# BOB_v1_02.net
KiCad netlist of a schematic drawn in EAGLE
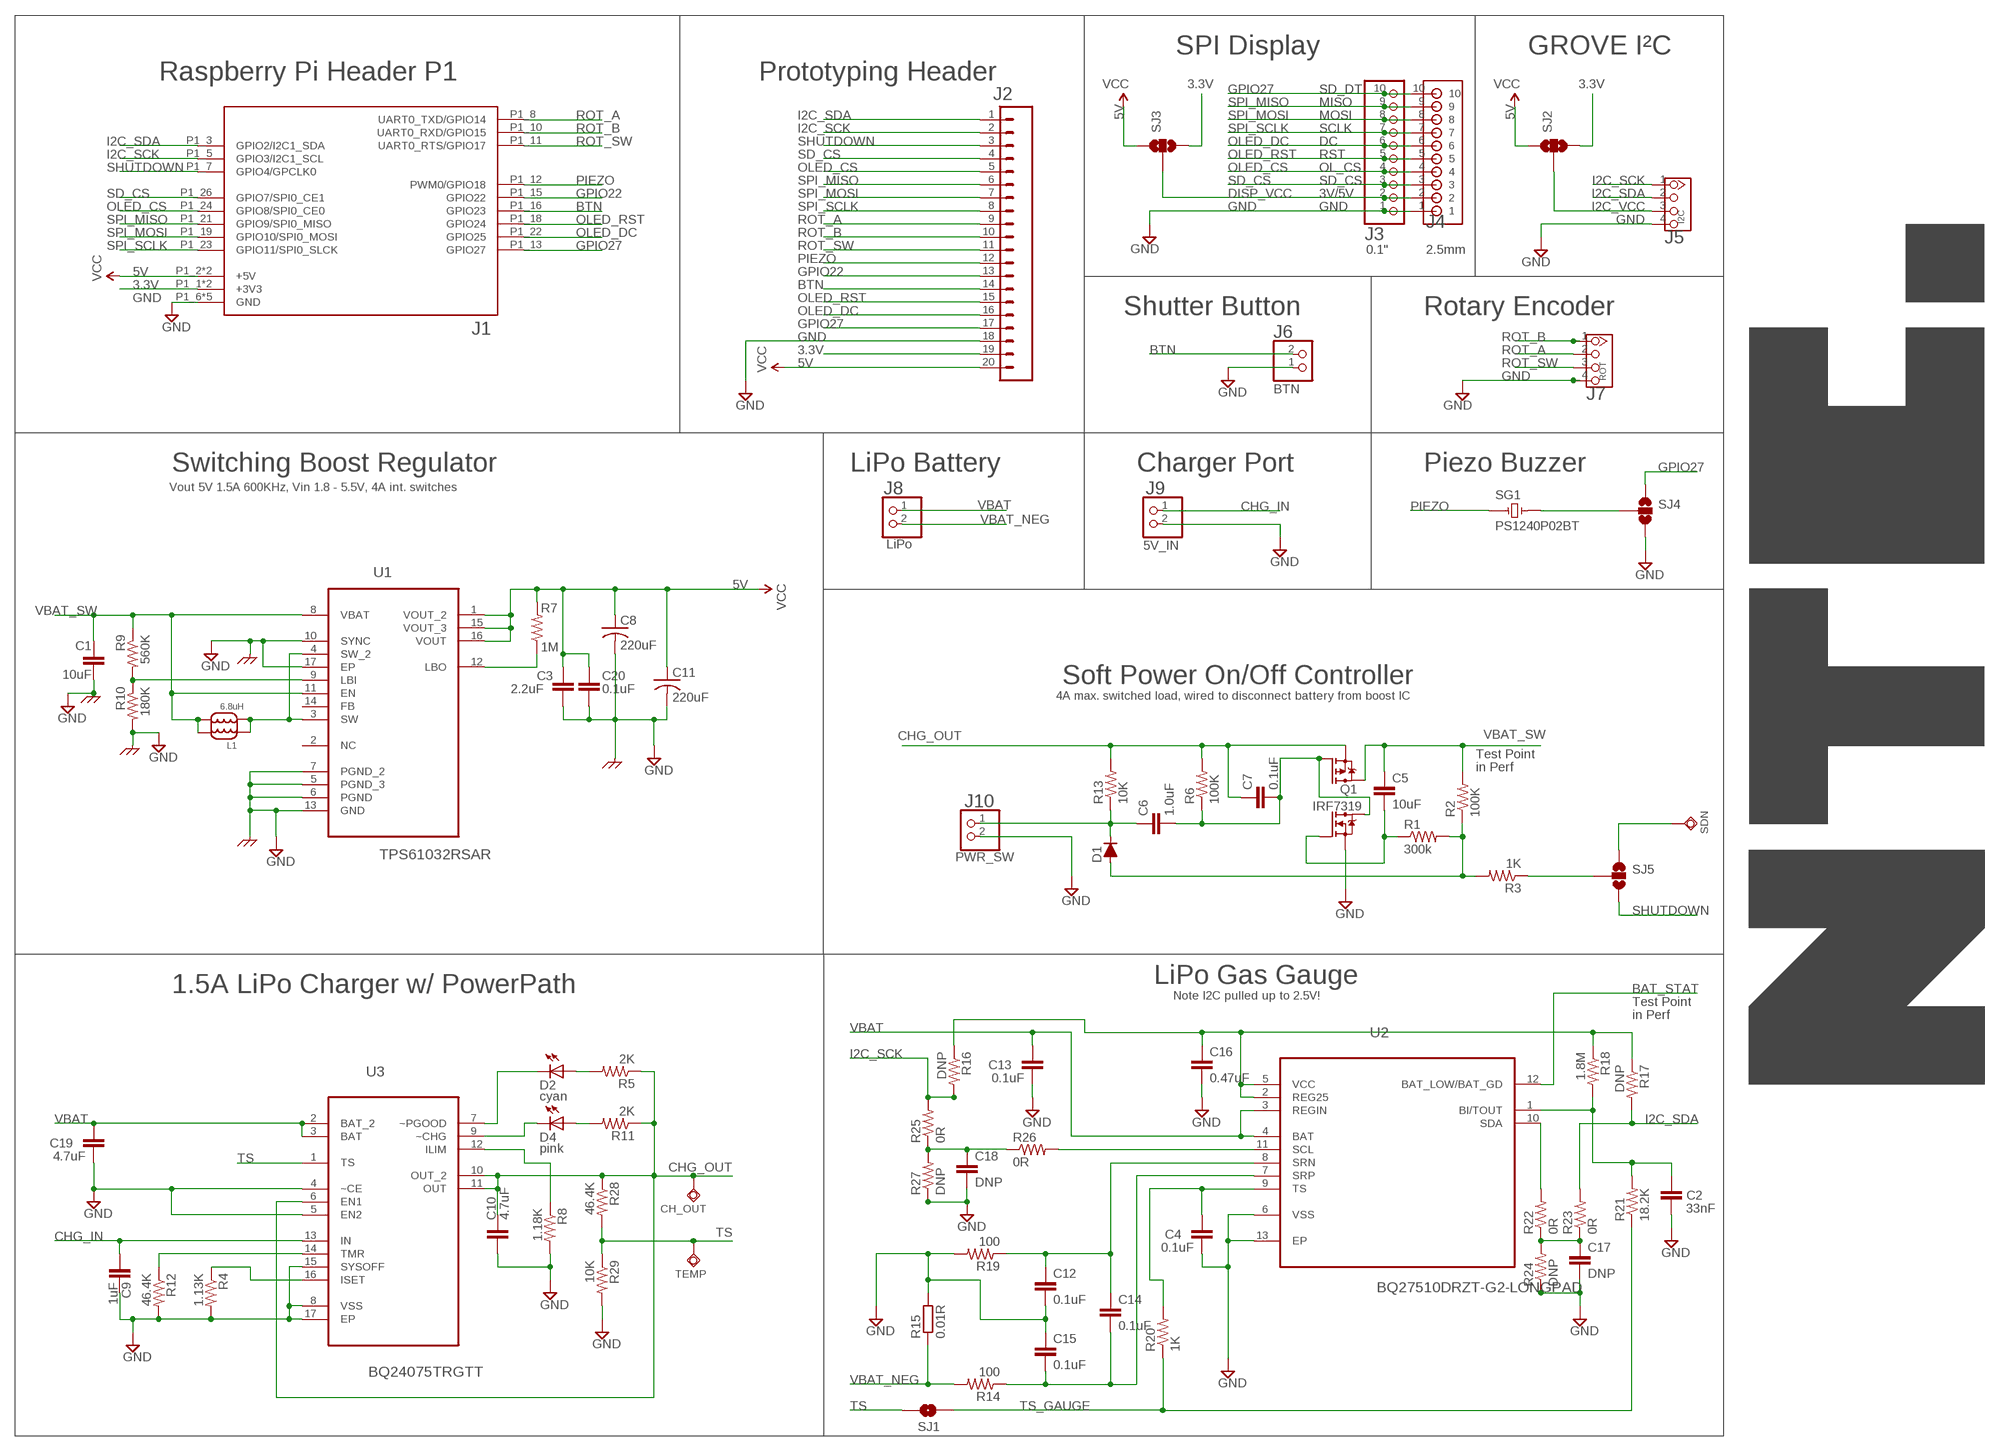
[diagram p0: schematic, sheet 1]

(export (version "E")
  (design (tool "Eeschema 10.0.6"))
  (components
    (comp (ref "C1")
      (value "10uF")
      (footprint "eagle-import:1206")
      (libsource (lib "eagle-import") (part "CAP1206"))
    )
    (comp (ref "C2")
      (value "33nF")
      (footprint "eagle-import:0603-CAP")
      (libsource (lib "eagle-import") (part "CAP0603-CAP"))
    )
    (comp (ref "C3")
      (value "2.2uF")
      (footprint "eagle-import:0603")
      (libsource (lib "eagle-import") (part "CAP0603"))
    )
    (comp (ref "C4")
      (value "0.1uF")
      (footprint "eagle-import:0603-CAP")
      (libsource (lib "eagle-import") (part "CAP0603-CAP"))
    )
    (comp (ref "C5")
      (value "10uF")
      (footprint "eagle-import:0603-CAP")
      (libsource (lib "eagle-import") (part "10UF-6.3V-20%(0603)"))
    )
    (comp (ref "C6")
      (value "1.0uF")
      (footprint "eagle-import:0603-CAP")
      (libsource (lib "eagle-import") (part "1.0UF-16V-10%(0603)"))
    )
    (comp (ref "C7")
      (value "0.1uF")
      (footprint "eagle-import:0603-CAP")
      (libsource (lib "eagle-import") (part "0.1UF-25V-5%(0603)"))
    )
    (comp (ref "C8")
      (value "220uF")
      (footprint "eagle-import:C1210")
      (libsource (lib "eagle-import") (part "C-USC1210"))
    )
    (comp (ref "C9")
      (value "1uF")
      (footprint "eagle-import:0603-CAP")
      (libsource (lib "eagle-import") (part "CAP0603-CAP"))
    )
    (comp (ref "C10")
      (value "4.7uF")
      (footprint "eagle-import:0603-CAP")
      (libsource (lib "eagle-import") (part "CAP0603-CAP"))
    )
    (comp (ref "C11")
      (value "220uF")
      (footprint "eagle-import:C1210")
      (libsource (lib "eagle-import") (part "C-USC1210"))
    )
    (comp (ref "C12")
      (value "0.1uF")
      (footprint "eagle-import:0603-CAP")
      (libsource (lib "eagle-import") (part "SparkFun-Capacitors_CAP0603-CAP"))
    )
    (comp (ref "C13")
      (value "0.1uF")
      (footprint "eagle-import:0603-CAP")
      (libsource (lib "eagle-import") (part "CAP0603-CAP"))
    )
    (comp (ref "C14")
      (value "0.1uF")
      (footprint "eagle-import:0603-CAP")
      (libsource (lib "eagle-import") (part "SparkFun-Capacitors_CAP0603-CAP"))
    )
    (comp (ref "C15")
      (value "0.1uF")
      (footprint "eagle-import:0603-CAP")
      (libsource (lib "eagle-import") (part "SparkFun-Capacitors_CAP0603-CAP"))
    )
    (comp (ref "C16")
      (value "0.47uF")
      (footprint "eagle-import:0603-CAP")
      (libsource (lib "eagle-import") (part "SparkFun-Capacitors_CAP0603-CAP"))
    )
    (comp (ref "C17")
      (value "DNP")
      (footprint "eagle-import:0603-CAP")
      (libsource (lib "eagle-import") (part "SparkFun-Capacitors_CAP0603-CAP"))
    )
    (comp (ref "C18")
      (value "DNP")
      (footprint "eagle-import:0603-CAP")
      (libsource (lib "eagle-import") (part "SparkFun-Capacitors_CAP0603-CAP"))
    )
    (comp (ref "C19")
      (value "4.7uF")
      (footprint "eagle-import:0603-CAP")
      (libsource (lib "eagle-import") (part "CAP0603-CAP"))
    )
    (comp (ref "C20")
      (value "0.1uF")
      (footprint "eagle-import:0603-CAP")
      (fields (field (name "PROD_ID") "CAP-00868"))
      (libsource (lib "eagle-import") (part "1.0UF-16V-10%(0603)"))
    )
    (comp (ref "CH_OUT")
      (value "TP1.2")
      (footprint "eagle-import:TP_1.2")
      (libsource (lib "eagle-import") (part "TP1.2"))
    )
    (comp (ref "D1")
      (value "D-FILL-SMB")
      (footprint "eagle-import:SMB")
      (libsource (lib "eagle-import") (part "D-FILL-SMB"))
    )
    (comp (ref "D2")
      (value "cyan")
      (footprint "eagle-import:LED-0603")
      (libsource (lib "eagle-import") (part "LED0603"))
    )
    (comp (ref "D4")
      (value "pink")
      (footprint "eagle-import:LED-0603")
      (libsource (lib "eagle-import") (part "LED0603"))
    )
    (comp (ref "J1")
      (value "PICAM_RPI-B-PICAM")
      (footprint "eagle-import:PICAM_RPI-B-PICAM")
      (libsource (lib "eagle-import") (part "PICAM_RPI-B-PICAM"))
    )
    (comp (ref "J2")
      (value "M20LOCK_LONGPADS")
      (footprint "eagle-import:1X20_LOCK_LONGPADS")
      (libsource (lib "eagle-import") (part "M20LOCK_LONGPADS"))
    )
    (comp (ref "J3")
      (value "PINHD-1X10")
      (footprint "eagle-import:1X10-BIG")
      (libsource (lib "eagle-import") (part "PINHD-1X10"))
    )
    (comp (ref "J4")
      (value "B10B-EH-A-RA")
      (footprint "eagle-import:S10B-EH")
      (libsource (lib "eagle-import") (part "B10B-EH-A-RA"))
    )
    (comp (ref "J5")
      (value "I2C")
      (footprint "eagle-import:4P-2.0")
      (libsource (lib "eagle-import") (part "TWIG-4P-2.0-2.0"))
    )
    (comp (ref "J6")
      (value "BTN")
      (footprint "eagle-import:PICAM_JST-PH-2-THM")
      (libsource (lib "eagle-import") (part "PICAM_JST_2PIN-THM"))
    )
    (comp (ref "J7")
      (value "ROT")
      (footprint "eagle-import:4P-2.0")
      (libsource (lib "eagle-import") (part "TWIG-4P-2.0-2.0"))
    )
    (comp (ref "J8")
      (value "LiPo")
      (footprint "eagle-import:PICAM_JST-PH-2-THM")
      (libsource (lib "eagle-import") (part "PICAM_JST_2PIN-THM"))
    )
    (comp (ref "J9")
      (value "5V_IN")
      (footprint "eagle-import:PICAM_JST-PH-2-THM")
      (libsource (lib "eagle-import") (part "PICAM_JST_2PIN-THM"))
    )
    (comp (ref "J10")
      (value "PWR_SW")
      (footprint "eagle-import:PICAM_JST-PH-2-THM")
      (libsource (lib "eagle-import") (part "PICAM_JST_2PIN-THM"))
    )
    (comp (ref "L1")
      (value "6.8uH")
      (footprint "eagle-import:SUMIDA_CDRH124")
      (libsource (lib "eagle-import") (part "SUMIDA_CDRH124CDRH124NP-6R8MC"))
    )
    (comp (ref "Q1")
      (value "IRF7319")
      (footprint "eagle-import:SO08-IRF")
      (libsource (lib "eagle-import") (part "IRF7319Q"))
    )
    (comp (ref "R1")
      (value "300k")
      (footprint "eagle-import:0603-RES")
      (libsource (lib "eagle-import") (part "SparkFun-Passives_RESISTOR0603-RES"))
    )
    (comp (ref "R2")
      (value "100K")
      (footprint "eagle-import:0603-RES")
      (libsource (lib "eagle-import") (part "SparkFun-Passives_RESISTOR0603-RES"))
    )
    (comp (ref "R3")
      (value "1K")
      (footprint "eagle-import:0603-RES")
      (libsource (lib "eagle-import") (part "SparkFun-Passives_RESISTOR0603-RES"))
    )
    (comp (ref "R4")
      (value "1.13K")
      (footprint "eagle-import:0603-RES")
      (libsource (lib "eagle-import") (part "RESISTOR0603-RES"))
    )
    (comp (ref "R5")
      (value "2K")
      (footprint "eagle-import:0603-RES")
      (libsource (lib "eagle-import") (part "RESISTOR0603-RES"))
    )
    (comp (ref "R6")
      (value "100K")
      (footprint "eagle-import:0603-RES")
      (libsource (lib "eagle-import") (part "SparkFun-Passives_RESISTOR0603-RES"))
    )
    (comp (ref "R7")
      (value "1M")
      (footprint "eagle-import:0603-RES")
      (libsource (lib "eagle-import") (part "RESISTOR0603-RES"))
    )
    (comp (ref "R8")
      (value "1.18K")
      (footprint "eagle-import:0603-RES")
      (libsource (lib "eagle-import") (part "RESISTOR0603-RES"))
    )
    (comp (ref "R9")
      (value "560K")
      (footprint "eagle-import:0603-RES")
      (libsource (lib "eagle-import") (part "RESISTOR0603-RES"))
    )
    (comp (ref "R10")
      (value "180K")
      (footprint "eagle-import:0603-RES")
      (libsource (lib "eagle-import") (part "RESISTOR0603-RES"))
    )
    (comp (ref "R11")
      (value "2K")
      (footprint "eagle-import:0603-RES")
      (libsource (lib "eagle-import") (part "RESISTOR0603-RES"))
    )
    (comp (ref "R12")
      (value "46.4K")
      (footprint "eagle-import:0603-RES")
      (libsource (lib "eagle-import") (part "RESISTOR0603-RES"))
    )
    (comp (ref "R13")
      (value "10K")
      (footprint "eagle-import:0603-RES")
      (libsource (lib "eagle-import") (part "SparkFun-Passives_RESISTOR0603-RES"))
    )
    (comp (ref "R14")
      (value "100")
      (footprint "eagle-import:0603-RES")
      (libsource (lib "eagle-import") (part "RESISTOR0603-RES"))
    )
    (comp (ref "R15")
      (value "0.01R")
      (footprint "eagle-import:R1206")
      (libsource (lib "eagle-import") (part "RESISTOR-1206"))
    )
    (comp (ref "R16")
      (value "DNP")
      (footprint "eagle-import:0603-RES")
      (libsource (lib "eagle-import") (part "RESISTOR0603-RES"))
    )
    (comp (ref "R17")
      (value "DNP")
      (footprint "eagle-import:0603-RES")
      (libsource (lib "eagle-import") (part "RESISTOR0603-RES"))
    )
    (comp (ref "R18")
      (value "1.8M")
      (footprint "eagle-import:0603-RES")
      (libsource (lib "eagle-import") (part "RESISTOR0603-RES"))
    )
    (comp (ref "R19")
      (value "100")
      (footprint "eagle-import:0603-RES")
      (libsource (lib "eagle-import") (part "RESISTOR0603-RES"))
    )
    (comp (ref "R20")
      (value "1K")
      (footprint "eagle-import:0603-RES")
      (libsource (lib "eagle-import") (part "SparkFun-Resistors_RESISTOR0603-RES"))
    )
    (comp (ref "R21")
      (value "18.2K")
      (footprint "eagle-import:0603-RES")
      (libsource (lib "eagle-import") (part "SparkFun-Resistors_RESISTOR0603-RES"))
    )
    (comp (ref "R22")
      (value "0R")
      (footprint "eagle-import:0603-RES")
      (libsource (lib "eagle-import") (part "SparkFun-Resistors_RESISTOR0603-RES"))
    )
    (comp (ref "R23")
      (value "0R")
      (footprint "eagle-import:0603-RES")
      (libsource (lib "eagle-import") (part "SparkFun-Resistors_RESISTOR0603-RES"))
    )
    (comp (ref "R24")
      (value "DNP")
      (footprint "eagle-import:0603-RES")
      (libsource (lib "eagle-import") (part "SparkFun-Resistors_RESISTOR0603-RES"))
    )
    (comp (ref "R25")
      (value "0R")
      (footprint "eagle-import:0603-RES")
      (libsource (lib "eagle-import") (part "SparkFun-Resistors_RESISTOR0603-RES"))
    )
    (comp (ref "R26")
      (value "0R")
      (footprint "eagle-import:0603-RES")
      (libsource (lib "eagle-import") (part "SparkFun-Resistors_RESISTOR0603-RES"))
    )
    (comp (ref "R27")
      (value "DNP")
      (footprint "eagle-import:0603-RES")
      (libsource (lib "eagle-import") (part "SparkFun-Resistors_RESISTOR0603-RES"))
    )
    (comp (ref "R28")
      (value "46.4K")
      (footprint "eagle-import:0603-RES")
      (libsource (lib "eagle-import") (part "RESISTOR0603-RES"))
    )
    (comp (ref "R29")
      (value "10K")
      (footprint "eagle-import:0603-RES")
      (libsource (lib "eagle-import") (part "RESISTOR0603-RES"))
    )
    (comp (ref "SDN")
      (value "TP1.2")
      (footprint "eagle-import:TP_1.2")
      (libsource (lib "eagle-import") (part "TP1.2"))
    )
    (comp (ref "SG1")
      (value "PS1240P02BT")
      (footprint "eagle-import:PS1240")
      (libsource (lib "eagle-import") (part "PS1240P02BT"))
    )
    (comp (ref "SJ1")
      (value "SOLDERJUMPER-OLDTRACE")
      (footprint "eagle-import:SJ_2S-TRACE")
      (libsource (lib "eagle-import") (part "SOLDERJUMPER-OLDTRACE"))
    )
    (comp (ref "SJ2")
      (value "SOLDERJUMPER_2WAYPASTE1&2")
      (footprint "eagle-import:SJ_3_PASTE1&2")
      (libsource (lib "eagle-import") (part "SOLDERJUMPER_2WAYPASTE1&2"))
    )
    (comp (ref "SJ3")
      (value "SOLDERJUMPER_2WAYPASTE2&3")
      (footprint "eagle-import:SJ_3_PASTE2&3")
      (libsource (lib "eagle-import") (part "SOLDERJUMPER_2WAYPASTE2&3"))
    )
    (comp (ref "SJ4")
      (value "SOLDERJUMPER_2WAYPASTE1&2")
      (footprint "eagle-import:SJ_3_PASTE1&2")
      (libsource (lib "eagle-import") (part "SOLDERJUMPER_2WAYPASTE1&2"))
    )
    (comp (ref "SJ5")
      (value "SOLDERJUMPER_2WAYPASTE2&3")
      (footprint "eagle-import:SJ_3_PASTE2&3")
      (libsource (lib "eagle-import") (part "SOLDERJUMPER_2WAYPASTE2&3"))
    )
    (comp (ref "TEMP")
      (value "TP1.2")
      (footprint "eagle-import:TP_1.2")
      (libsource (lib "eagle-import") (part "TP1.2"))
    )
    (comp (ref "U1")
      (value "TPS61032RSAR")
      (footprint "eagle-import:QFN65P400X400X100-17N")
      (libsource (lib "eagle-import") (part "TPS61032RSAR"))
    )
    (comp (ref "U2")
      (value "BQ27510DRZT-G2-LONGPAD")
      (footprint "eagle-import:SON40P400X250X100-13N+LONGPAD")
      (fields (field (name "MPN") "BQ27510DRZT-G2") (field (name "SUPPLIER") "Texas Inustruments"))
      (libsource (lib "eagle-import") (part "BQ27510DRZT-G2-LONGPAD"))
    )
    (comp (ref "U3")
      (value "BQ24075TRGTT")
      (footprint "eagle-import:QFN50P300X300X100-17N")
      (libsource (lib "eagle-import") (part "BQ24075TRGTT"))
    )
  )
  (nets
    (net (code "1") (name "3.3V") (class "Default")
      (node (ref "J1") (pin "P1_1") (pinfunction "+3V3_P1_1") (pintype "power_in"))
      (node (ref "J1") (pin "P1_17") (pinfunction "+3V3_P1_17") (pintype "power_in"))
      (node (ref "J2") (pin "19") (pinfunction "19_19") (pintype "passive"))
      (node (ref "SJ2") (pin "3") (pinfunction "3_3") (pintype "passive"))
      (node (ref "SJ3") (pin "3") (pinfunction "3_3") (pintype "passive"))
    )
    (net (code "2") (name "5V") (class "Default")
      (node (ref "C11") (pin "1") (pinfunction "1_1") (pintype "passive"))
      (node (ref "C20") (pin "1") (pinfunction "1_1") (pintype "passive"))
      (node (ref "C3") (pin "1") (pinfunction "1_1") (pintype "passive"))
      (node (ref "C8") (pin "1") (pinfunction "1_1") (pintype "passive"))
      (node (ref "J1") (pin "P1_2") (pinfunction "+5V_P1_2") (pintype "power_in"))
      (node (ref "J1") (pin "P1_4") (pinfunction "+5V_P1_4") (pintype "power_in"))
      (node (ref "J2") (pin "20") (pinfunction "20_20") (pintype "passive"))
      (node (ref "R7") (pin "2") (pinfunction "2_2") (pintype "passive"))
      (node (ref "SJ2") (pin "1") (pinfunction "1_1") (pintype "passive"))
      (node (ref "SJ3") (pin "1") (pinfunction "1_1") (pintype "passive"))
      (node (ref "U1") (pin "1") (pinfunction "VOUT_2_1") (pintype "output"))
      (node (ref "U1") (pin "15") (pinfunction "VOUT_3_15") (pintype "output"))
      (node (ref "U1") (pin "16") (pinfunction "VOUT_16") (pintype "output"))
    )
    (net (code "3") (name "BAT_STAT") (class "Default")
      (node (ref "U2") (pin "12") (pinfunction "BAT_LOW/BAT_GD_12") (pintype "output"))
    )
    (net (code "4") (name "BTN") (class "Default")
      (node (ref "J1") (pin "P1_16") (pinfunction "GPIO23_P1_16") (pintype "bidirectional"))
      (node (ref "J2") (pin "14") (pinfunction "14_14") (pintype "passive"))
      (node (ref "J6") (pin "2") (pinfunction "1_2") (pintype "passive"))
    )
    (net (code "5") (name "CHG_IN") (class "Default")
      (node (ref "C9") (pin "1") (pinfunction "1_1") (pintype "passive"))
      (node (ref "J9") (pin "1") (pinfunction "2_1") (pintype "passive"))
      (node (ref "U3") (pin "13") (pinfunction "IN_13") (pintype "input"))
    )
    (net (code "6") (name "CHG_OUT") (class "Default")
      (node (ref "C10") (pin "1") (pinfunction "1_1") (pintype "passive"))
      (node (ref "C7") (pin "1") (pinfunction "1_1") (pintype "passive"))
      (node (ref "CH_OUT") (pin "1") (pinfunction "TP_1") (pintype "passive"))
      (node (ref "Q1") (pin "3") (pinfunction "P-S2_3") (pintype "passive"))
      (node (ref "R11") (pin "1") (pinfunction "1_1") (pintype "passive"))
      (node (ref "R13") (pin "2") (pinfunction "2_2") (pintype "passive"))
      (node (ref "R28") (pin "1") (pinfunction "1_1") (pintype "passive"))
      (node (ref "R5") (pin "1") (pinfunction "1_1") (pintype "passive"))
      (node (ref "R6") (pin "2") (pinfunction "2_2") (pintype "passive"))
      (node (ref "U3") (pin "10") (pinfunction "OUT_2_10") (pintype "output"))
      (node (ref "U3") (pin "11") (pinfunction "OUT_11") (pintype "output"))
      (node (ref "U3") (pin "6") (pinfunction "EN1_6") (pintype "input"))
    )
    (net (code "7") (name "DISP_VCC") (class "Default")
      (node (ref "J3") (pin "2") (pinfunction "2_2") (pintype "passive"))
      (node (ref "J4") (pin "2") (pinfunction "2_2") (pintype "bidirectional"))
      (node (ref "SJ3") (pin "2") (pinfunction "2_2") (pintype "passive"))
    )
    (net (code "8") (name "GND") (class "Default")
      (node (ref "C1") (pin "2") (pinfunction "2_2") (pintype "passive"))
      (node (ref "C10") (pin "2") (pinfunction "2_2") (pintype "passive"))
      (node (ref "C11") (pin "2") (pinfunction "2_2") (pintype "passive"))
      (node (ref "C12") (pin "2") (pinfunction "2_2") (pintype "passive"))
      (node (ref "C13") (pin "2") (pinfunction "2_2") (pintype "passive"))
      (node (ref "C15") (pin "1") (pinfunction "1_1") (pintype "passive"))
      (node (ref "C16") (pin "2") (pinfunction "2_2") (pintype "passive"))
      (node (ref "C17") (pin "2") (pinfunction "2_2") (pintype "passive"))
      (node (ref "C18") (pin "2") (pinfunction "2_2") (pintype "passive"))
      (node (ref "C19") (pin "2") (pinfunction "2_2") (pintype "passive"))
      (node (ref "C2") (pin "2") (pinfunction "2_2") (pintype "passive"))
      (node (ref "C20") (pin "2") (pinfunction "2_2") (pintype "passive"))
      (node (ref "C3") (pin "2") (pinfunction "2_2") (pintype "passive"))
      (node (ref "C4") (pin "2") (pinfunction "2_2") (pintype "passive"))
      (node (ref "C8") (pin "2") (pinfunction "2_2") (pintype "passive"))
      (node (ref "C9") (pin "2") (pinfunction "2_2") (pintype "passive"))
      (node (ref "J1") (pin "P1_14") (pinfunction "GND_P1_14") (pintype "power_in"))
      (node (ref "J1") (pin "P1_20") (pinfunction "GND_P1_20") (pintype "power_in"))
      (node (ref "J1") (pin "P1_25") (pinfunction "GND_P1_25") (pintype "power_in"))
      (node (ref "J1") (pin "P1_6") (pinfunction "GND_P1_6") (pintype "power_in"))
      (node (ref "J1") (pin "P1_9") (pinfunction "GND_P1_9") (pintype "power_in"))
      (node (ref "J10") (pin "2") (pinfunction "1_2") (pintype "passive"))
      (node (ref "J2") (pin "18") (pinfunction "18_18") (pintype "passive"))
      (node (ref "J3") (pin "1") (pinfunction "1_1") (pintype "passive"))
      (node (ref "J4") (pin "1") (pinfunction "1_1") (pintype "bidirectional"))
      (node (ref "J5") (pin "4") (pinfunction "4_4") (pintype "bidirectional"))
      (node (ref "J6") (pin "1") (pinfunction "2_1") (pintype "passive"))
      (node (ref "J7") (pin "4") (pinfunction "4_4") (pintype "bidirectional"))
      (node (ref "J9") (pin "2") (pinfunction "1_2") (pintype "passive"))
      (node (ref "Q1") (pin "1") (pinfunction "N-S1_1") (pintype "passive"))
      (node (ref "R10") (pin "2") (pinfunction "2_2") (pintype "passive"))
      (node (ref "R12") (pin "2") (pinfunction "2_2") (pintype "passive"))
      (node (ref "R15") (pin "2") (pinfunction "2_2") (pintype "passive"))
      (node (ref "R19") (pin "2") (pinfunction "2_2") (pintype "passive"))
      (node (ref "R24") (pin "1") (pinfunction "1_1") (pintype "passive"))
      (node (ref "R27") (pin "1") (pinfunction "1_1") (pintype "passive"))
      (node (ref "R29") (pin "2") (pinfunction "2_2") (pintype "passive"))
      (node (ref "R4") (pin "2") (pinfunction "2_2") (pintype "passive"))
      (node (ref "R8") (pin "2") (pinfunction "2_2") (pintype "passive"))
      (node (ref "SJ4") (pin "3") (pinfunction "3_3") (pintype "passive"))
      (node (ref "U1") (pin "10") (pinfunction "SYNC_10") (pintype "input"))
      (node (ref "U1") (pin "13") (pinfunction "GND_13") (pintype "passive"))
      (node (ref "U1") (pin "17") (pinfunction "EP_17") (pintype "passive"))
      (node (ref "U1") (pin "5") (pinfunction "PGND_3_5") (pintype "passive"))
      (node (ref "U1") (pin "6") (pinfunction "PGND_6") (pintype "passive"))
      (node (ref "U1") (pin "7") (pinfunction "PGND_2_7") (pintype "passive"))
      (node (ref "U2") (pin "13") (pinfunction "EP_13") (pintype "passive"))
      (node (ref "U2") (pin "6") (pinfunction "VSS_6") (pintype "power_in"))
      (node (ref "U3") (pin "15") (pinfunction "SYSOFF_15") (pintype "input"))
      (node (ref "U3") (pin "17") (pinfunction "EP_17") (pintype "passive"))
      (node (ref "U3") (pin "4") (pinfunction "~{CE}_4") (pintype "input"))
      (node (ref "U3") (pin "5") (pinfunction "EN2_5") (pintype "input"))
      (node (ref "U3") (pin "8") (pinfunction "VSS_8") (pintype "passive"))
    )
    (net (code "9") (name "GPIO22") (class "Default")
      (node (ref "J1") (pin "P1_15") (pinfunction "GPIO22_P1_15") (pintype "bidirectional"))
      (node (ref "J2") (pin "13") (pinfunction "13_13") (pintype "passive"))
    )
    (net (code "10") (name "GPIO27") (class "Default")
      (node (ref "J1") (pin "P1_13") (pinfunction "GPIO27_P1_13") (pintype "bidirectional"))
      (node (ref "J2") (pin "17") (pinfunction "17_17") (pintype "passive"))
      (node (ref "J3") (pin "10") (pinfunction "10_10") (pintype "passive"))
      (node (ref "J4") (pin "10") (pinfunction "10_10") (pintype "bidirectional"))
      (node (ref "SJ4") (pin "1") (pinfunction "1_1") (pintype "passive"))
    )
    (net (code "11") (name "I2C_SCK") (class "Default")
      (node (ref "J1") (pin "P1_5") (pinfunction "GPIO3/I2C1_SCL_P1_5") (pintype "bidirectional"))
      (node (ref "J2") (pin "2") (pinfunction "2_2") (pintype "passive"))
      (node (ref "J5") (pin "1") (pinfunction "1_1") (pintype "bidirectional"))
      (node (ref "R16") (pin "2") (pinfunction "2_2") (pintype "passive"))
      (node (ref "R25") (pin "2") (pinfunction "2_2") (pintype "passive"))
    )
    (net (code "12") (name "I2C_SDA") (class "Default")
      (node (ref "J1") (pin "P1_3") (pinfunction "GPIO2/I2C1_SDA_P1_3") (pintype "bidirectional"))
      (node (ref "J2") (pin "1") (pinfunction "1_1") (pintype "passive"))
      (node (ref "J5") (pin "2") (pinfunction "2_2") (pintype "bidirectional"))
      (node (ref "R17") (pin "2") (pinfunction "2_2") (pintype "passive"))
      (node (ref "R23") (pin "2") (pinfunction "2_2") (pintype "passive"))
    )
    (net (code "13") (name "I2C_VCC") (class "Default")
      (node (ref "J5") (pin "3") (pinfunction "3_3") (pintype "bidirectional"))
      (node (ref "SJ2") (pin "2") (pinfunction "2_2") (pintype "passive"))
    )
    (net (code "14") (name "Net-(C17-Pad1)") (class "Default")
      (node (ref "C17") (pin "1") (pinfunction "1_1") (pintype "passive"))
      (node (ref "R22") (pin "1") (pinfunction "1_1") (pintype "passive"))
      (node (ref "R23") (pin "1") (pinfunction "1_1") (pintype "passive"))
      (node (ref "R24") (pin "2") (pinfunction "2_2") (pintype "passive"))
    )
    (net (code "15") (name "Net-(C18-Pad1)") (class "Default")
      (node (ref "C18") (pin "1") (pinfunction "1_1") (pintype "passive"))
      (node (ref "R25") (pin "1") (pinfunction "1_1") (pintype "passive"))
      (node (ref "R26") (pin "1") (pinfunction "1_1") (pintype "passive"))
      (node (ref "R27") (pin "2") (pinfunction "2_2") (pintype "passive"))
    )
    (net (code "16") (name "Net-(D1-A)") (class "Default")
      (node (ref "D1") (pin "2") (pinfunction "A_2") (pintype "passive"))
      (node (ref "R1") (pin "2") (pinfunction "2_2") (pintype "passive"))
      (node (ref "R2") (pin "1") (pinfunction "1_1") (pintype "passive"))
      (node (ref "R3") (pin "2") (pinfunction "2_2") (pintype "passive"))
    )
    (net (code "17") (name "Net-(D1-C)") (class "Default")
      (node (ref "C6") (pin "1") (pinfunction "1_1") (pintype "passive"))
      (node (ref "D1") (pin "1") (pinfunction "C_1") (pintype "passive"))
      (node (ref "J10") (pin "1") (pinfunction "2_1") (pintype "passive"))
      (node (ref "R13") (pin "1") (pinfunction "1_1") (pintype "passive"))
    )
    (net (code "18") (name "Net-(D2-PadA)") (class "Default")
      (node (ref "D2") (pin "A") (pinfunction "A_A") (pintype "passive"))
      (node (ref "R5") (pin "2") (pinfunction "2_2") (pintype "passive"))
    )
    (net (code "19") (name "Net-(D4-PadA)") (class "Default")
      (node (ref "D4") (pin "A") (pinfunction "A_A") (pintype "passive"))
      (node (ref "R11") (pin "2") (pinfunction "2_2") (pintype "passive"))
    )
    (net (code "20") (name "Net-(Q1-N-G1)") (class "Default")
      (node (ref "C5") (pin "2") (pinfunction "2_2") (pintype "passive"))
      (node (ref "Q1") (pin "2") (pinfunction "N-G1_2") (pintype "passive"))
      (node (ref "R1") (pin "1") (pinfunction "1_1") (pintype "passive"))
    )
    (net (code "21") (name "Net-(Q1-P-G2)") (class "Default")
      (node (ref "C6") (pin "2") (pinfunction "2_2") (pintype "passive"))
      (node (ref "C7") (pin "2") (pinfunction "2_2") (pintype "passive"))
      (node (ref "Q1") (pin "4") (pinfunction "P-G2_4") (pintype "passive"))
      (node (ref "Q1") (pin "7") (pinfunction "N-D1_7") (pintype "passive"))
      (node (ref "Q1") (pin "8") (pinfunction "N-D1_8") (pintype "passive"))
      (node (ref "R6") (pin "1") (pinfunction "1_1") (pintype "passive"))
    )
    (net (code "22") (name "Net-(R3-Pad1)") (class "Default")
      (node (ref "R3") (pin "1") (pinfunction "1_1") (pintype "passive"))
      (node (ref "SJ5") (pin "2") (pinfunction "2_2") (pintype "passive"))
    )
    (net (code "23") (name "Net-(SDN-TP)") (class "Default")
      (node (ref "SDN") (pin "1") (pinfunction "TP_1") (pintype "passive"))
      (node (ref "SJ5") (pin "1") (pinfunction "1_1") (pintype "passive"))
    )
    (net (code "24") (name "Net-(SG1-2)") (class "Default")
      (node (ref "SG1") (pin "P$2") (pinfunction "2_P$2") (pintype "passive"))
      (node (ref "SJ4") (pin "2") (pinfunction "2_2") (pintype "passive"))
    )
    (net (code "25") (name "Net-(U1-LBI)") (class "Default")
      (node (ref "R10") (pin "1") (pinfunction "1_1") (pintype "passive"))
      (node (ref "R9") (pin "2") (pinfunction "2_2") (pintype "passive"))
      (node (ref "U1") (pin "9") (pinfunction "LBI_9") (pintype "input"))
    )
    (net (code "26") (name "Net-(U1-LBO)") (class "Default")
      (node (ref "R7") (pin "1") (pinfunction "1_1") (pintype "passive"))
      (node (ref "U1") (pin "12") (pinfunction "LBO_12") (pintype "output"))
    )
    (net (code "27") (name "Net-(U1-SW)") (class "Default")
      (node (ref "L1") (pin "P$3") (pinfunction "2_P$3") (pintype "passive"))
      (node (ref "L1") (pin "P$4") (pinfunction "2_P$4") (pintype "passive"))
      (node (ref "U1") (pin "3") (pinfunction "SW_3") (pintype "input"))
      (node (ref "U1") (pin "4") (pinfunction "SW_2_4") (pintype "input"))
    )
    (net (code "28") (name "Net-(U2-BI{slash}TOUT)") (class "Default")
      (node (ref "C2") (pin "1") (pinfunction "1_1") (pintype "passive"))
      (node (ref "R18") (pin "2") (pinfunction "2_2") (pintype "passive"))
      (node (ref "R21") (pin "2") (pinfunction "2_2") (pintype "passive"))
      (node (ref "U2") (pin "1") (pinfunction "BI/TOUT_1") (pintype "bidirectional"))
    )
    (net (code "29") (name "Net-(U2-REG25)") (class "Default")
      (node (ref "C16") (pin "1") (pinfunction "1_1") (pintype "passive"))
      (node (ref "R16") (pin "1") (pinfunction "1_1") (pintype "passive"))
      (node (ref "R17") (pin "1") (pinfunction "1_1") (pintype "passive"))
      (node (ref "R18") (pin "1") (pinfunction "1_1") (pintype "passive"))
      (node (ref "U2") (pin "2") (pinfunction "REG25_2") (pintype "power_in"))
      (node (ref "U2") (pin "5") (pinfunction "VCC_5") (pintype "power_in"))
    )
    (net (code "30") (name "Net-(U2-SCL)") (class "Default")
      (node (ref "R26") (pin "2") (pinfunction "2_2") (pintype "passive"))
      (node (ref "U2") (pin "11") (pinfunction "SCL_11") (pintype "input"))
    )
    (net (code "31") (name "Net-(U2-SDA)") (class "Default")
      (node (ref "R22") (pin "2") (pinfunction "2_2") (pintype "passive"))
      (node (ref "U2") (pin "10") (pinfunction "SDA_10") (pintype "bidirectional"))
    )
    (net (code "32") (name "Net-(U2-SRN)") (class "Default")
      (node (ref "C12") (pin "1") (pinfunction "1_1") (pintype "passive"))
      (node (ref "C14") (pin "1") (pinfunction "1_1") (pintype "passive"))
      (node (ref "R19") (pin "1") (pinfunction "1_1") (pintype "passive"))
      (node (ref "U2") (pin "8") (pinfunction "SRN_8") (pintype "input"))
    )
    (net (code "33") (name "Net-(U2-SRP)") (class "Default")
      (node (ref "C14") (pin "2") (pinfunction "2_2") (pintype "passive"))
      (node (ref "C15") (pin "2") (pinfunction "2_2") (pintype "passive"))
      (node (ref "R14") (pin "1") (pinfunction "1_1") (pintype "passive"))
      (node (ref "U2") (pin "7") (pinfunction "SRP_7") (pintype "input"))
    )
    (net (code "34") (name "Net-(U2-TS)") (class "Default")
      (node (ref "C4") (pin "1") (pinfunction "1_1") (pintype "passive"))
      (node (ref "R20") (pin "2") (pinfunction "2_2") (pintype "passive"))
      (node (ref "U2") (pin "9") (pinfunction "TS_9") (pintype "input"))
    )
    (net (code "35") (name "Net-(U3-ILIM)") (class "Default")
      (node (ref "R8") (pin "1") (pinfunction "1_1") (pintype "passive"))
      (node (ref "U3") (pin "12") (pinfunction "ILIM_12") (pintype "output"))
    )
    (net (code "36") (name "Net-(U3-ISET)") (class "Default")
      (node (ref "R4") (pin "1") (pinfunction "1_1") (pintype "passive"))
      (node (ref "U3") (pin "16") (pinfunction "ISET_16") (pintype "bidirectional"))
    )
    (net (code "37") (name "Net-(U3-TMR)") (class "Default")
      (node (ref "R12") (pin "1") (pinfunction "1_1") (pintype "passive"))
      (node (ref "U3") (pin "14") (pinfunction "TMR_14") (pintype "input"))
    )
    (net (code "38") (name "Net-(U3-~{CHG})") (class "Default")
      (node (ref "D4") (pin "C") (pinfunction "C_C") (pintype "passive"))
      (node (ref "U3") (pin "9") (pinfunction "~{CHG}_9") (pintype "output"))
    )
    (net (code "39") (name "Net-(U3-~{PGOOD})") (class "Default")
      (node (ref "D2") (pin "C") (pinfunction "C_C") (pintype "passive"))
      (node (ref "U3") (pin "7") (pinfunction "~{PGOOD}_7") (pintype "output"))
    )
    (net (code "40") (name "OLED_CS") (class "Default")
      (node (ref "J1") (pin "P1_24") (pinfunction "GPIO8/SPI0_CE0_P1_24") (pintype "bidirectional"))
      (node (ref "J2") (pin "5") (pinfunction "5_5") (pintype "passive"))
      (node (ref "J3") (pin "4") (pinfunction "4_4") (pintype "passive"))
      (node (ref "J4") (pin "4") (pinfunction "4_4") (pintype "bidirectional"))
    )
    (net (code "41") (name "OLED_DC") (class "Default")
      (node (ref "J1") (pin "P1_22") (pinfunction "GPIO25_P1_22") (pintype "bidirectional"))
      (node (ref "J2") (pin "16") (pinfunction "16_16") (pintype "passive"))
      (node (ref "J3") (pin "6") (pinfunction "6_6") (pintype "passive"))
      (node (ref "J4") (pin "6") (pinfunction "6_6") (pintype "bidirectional"))
    )
    (net (code "42") (name "OLED_RST") (class "Default")
      (node (ref "J1") (pin "P1_18") (pinfunction "GPIO24_P1_18") (pintype "bidirectional"))
      (node (ref "J2") (pin "15") (pinfunction "15_15") (pintype "passive"))
      (node (ref "J3") (pin "5") (pinfunction "5_5") (pintype "passive"))
      (node (ref "J4") (pin "5") (pinfunction "5_5") (pintype "bidirectional"))
    )
    (net (code "43") (name "PIEZO") (class "Default")
      (node (ref "J1") (pin "P1_12") (pinfunction "PWM0/GPIO18_P1_12") (pintype "bidirectional"))
      (node (ref "J2") (pin "12") (pinfunction "12_12") (pintype "passive"))
      (node (ref "SG1") (pin "P$1") (pinfunction "1_P$1") (pintype "passive"))
    )
    (net (code "44") (name "ROT_A") (class "Default")
      (node (ref "J1") (pin "P1_8") (pinfunction "UART0_TXD/GPIO14_P1_8") (pintype "bidirectional"))
      (node (ref "J2") (pin "9") (pinfunction "9_9") (pintype "passive"))
      (node (ref "J7") (pin "2") (pinfunction "2_2") (pintype "bidirectional"))
    )
    (net (code "45") (name "ROT_B") (class "Default")
      (node (ref "J1") (pin "P1_10") (pinfunction "UART0_RXD/GPIO15_P1_10") (pintype "bidirectional"))
      (node (ref "J2") (pin "10") (pinfunction "10_10") (pintype "passive"))
      (node (ref "J7") (pin "1") (pinfunction "1_1") (pintype "bidirectional"))
    )
    (net (code "46") (name "ROT_SW") (class "Default")
      (node (ref "J1") (pin "P1_11") (pinfunction "UART0_RTS/GPIO17_P1_11") (pintype "bidirectional"))
      (node (ref "J2") (pin "11") (pinfunction "11_11") (pintype "passive"))
      (node (ref "J7") (pin "3") (pinfunction "3_3") (pintype "bidirectional"))
    )
    (net (code "47") (name "SD_CS") (class "Default")
      (node (ref "J1") (pin "P1_26") (pinfunction "GPIO7/SPI0_CE1_P1_26") (pintype "bidirectional"))
      (node (ref "J2") (pin "4") (pinfunction "4_4") (pintype "passive"))
      (node (ref "J3") (pin "3") (pinfunction "3_3") (pintype "passive"))
      (node (ref "J4") (pin "3") (pinfunction "3_3") (pintype "bidirectional"))
    )
    (net (code "48") (name "SHUTDOWN") (class "Default")
      (node (ref "J1") (pin "P1_7") (pinfunction "GPIO4/GPCLK0_P1_7") (pintype "bidirectional"))
      (node (ref "J2") (pin "3") (pinfunction "3_3") (pintype "passive"))
      (node (ref "SJ5") (pin "3") (pinfunction "3_3") (pintype "passive"))
    )
    (net (code "49") (name "SPI_MISO") (class "Default")
      (node (ref "J1") (pin "P1_21") (pinfunction "GPIO9/SPI0_MISO_P1_21") (pintype "bidirectional"))
      (node (ref "J2") (pin "6") (pinfunction "6_6") (pintype "passive"))
      (node (ref "J3") (pin "9") (pinfunction "9_9") (pintype "passive"))
      (node (ref "J4") (pin "9") (pinfunction "9_9") (pintype "bidirectional"))
    )
    (net (code "50") (name "SPI_MOSI") (class "Default")
      (node (ref "J1") (pin "P1_19") (pinfunction "GPIO10/SPI0_MOSI_P1_19") (pintype "bidirectional"))
      (node (ref "J2") (pin "7") (pinfunction "7_7") (pintype "passive"))
      (node (ref "J3") (pin "8") (pinfunction "8_8") (pintype "passive"))
      (node (ref "J4") (pin "8") (pinfunction "8_8") (pintype "bidirectional"))
    )
    (net (code "51") (name "SPI_SCLK") (class "Default")
      (node (ref "J1") (pin "P1_23") (pinfunction "GPIO11/SPI0_SLCK_P1_23") (pintype "bidirectional"))
      (node (ref "J2") (pin "8") (pinfunction "8_8") (pintype "passive"))
      (node (ref "J3") (pin "7") (pinfunction "7_7") (pintype "passive"))
      (node (ref "J4") (pin "7") (pinfunction "7_7") (pintype "bidirectional"))
    )
    (net (code "52") (name "TS") (class "Default")
      (node (ref "R28") (pin "2") (pinfunction "2_2") (pintype "passive"))
      (node (ref "R29") (pin "1") (pinfunction "1_1") (pintype "passive"))
      (node (ref "SJ1") (pin "1") (pinfunction "1_1") (pintype "passive"))
      (node (ref "TEMP") (pin "1") (pinfunction "TP_1") (pintype "passive"))
      (node (ref "U3") (pin "1") (pinfunction "TS_1") (pintype "bidirectional"))
    )
    (net (code "53") (name "TS_GAUGE") (class "Default")
      (node (ref "R20") (pin "1") (pinfunction "1_1") (pintype "passive"))
      (node (ref "R21") (pin "1") (pinfunction "1_1") (pintype "passive"))
      (node (ref "SJ1") (pin "2") (pinfunction "2_2") (pintype "passive"))
    )
    (net (code "54") (name "VBAT") (class "Default")
      (node (ref "C13") (pin "1") (pinfunction "1_1") (pintype "passive"))
      (node (ref "C19") (pin "1") (pinfunction "1_1") (pintype "passive"))
      (node (ref "J8") (pin "1") (pinfunction "2_1") (pintype "passive"))
      (node (ref "U2") (pin "3") (pinfunction "REGIN_3") (pintype "power_in"))
      (node (ref "U2") (pin "4") (pinfunction "BAT_4") (pintype "input"))
      (node (ref "U3") (pin "2") (pinfunction "BAT_2_2") (pintype "bidirectional"))
      (node (ref "U3") (pin "3") (pinfunction "BAT_3") (pintype "bidirectional"))
    )
    (net (code "55") (name "VBAT_NEG") (class "Default")
      (node (ref "J8") (pin "2") (pinfunction "1_2") (pintype "passive"))
      (node (ref "R14") (pin "2") (pinfunction "2_2") (pintype "passive"))
      (node (ref "R15") (pin "1") (pinfunction "1_1") (pintype "passive"))
    )
    (net (code "56") (name "VBAT_SW") (class "Default")
      (node (ref "C1") (pin "1") (pinfunction "1_1") (pintype "passive"))
      (node (ref "C5") (pin "1") (pinfunction "1_1") (pintype "passive"))
      (node (ref "L1") (pin "P$1") (pinfunction "1_P$1") (pintype "passive"))
      (node (ref "L1") (pin "P$2") (pinfunction "1_P$2") (pintype "passive"))
      (node (ref "Q1") (pin "5") (pinfunction "P-D2_5") (pintype "passive"))
      (node (ref "Q1") (pin "6") (pinfunction "P-D2_6") (pintype "passive"))
      (node (ref "R2") (pin "2") (pinfunction "2_2") (pintype "passive"))
      (node (ref "R9") (pin "1") (pinfunction "1_1") (pintype "passive"))
      (node (ref "U1") (pin "11") (pinfunction "EN_11") (pintype "input"))
      (node (ref "U1") (pin "8") (pinfunction "VBAT_8") (pintype "input"))
    )
    (net (code "57") (name "unconnected-(U1-FB-Pad14)") (class "Default")
      (node (ref "U1") (pin "14") (pinfunction "FB_14") (pintype "input"))
    )
    (net (code "58") (name "unconnected-(U1-NC-Pad2)") (class "Default")
      (node (ref "U1") (pin "2") (pinfunction "NC_2") (pintype "no_connect"))
    )
  )
)
